# tuggerTrackerV1.net
KiCad netlist of a schematic drawn in EAGLE
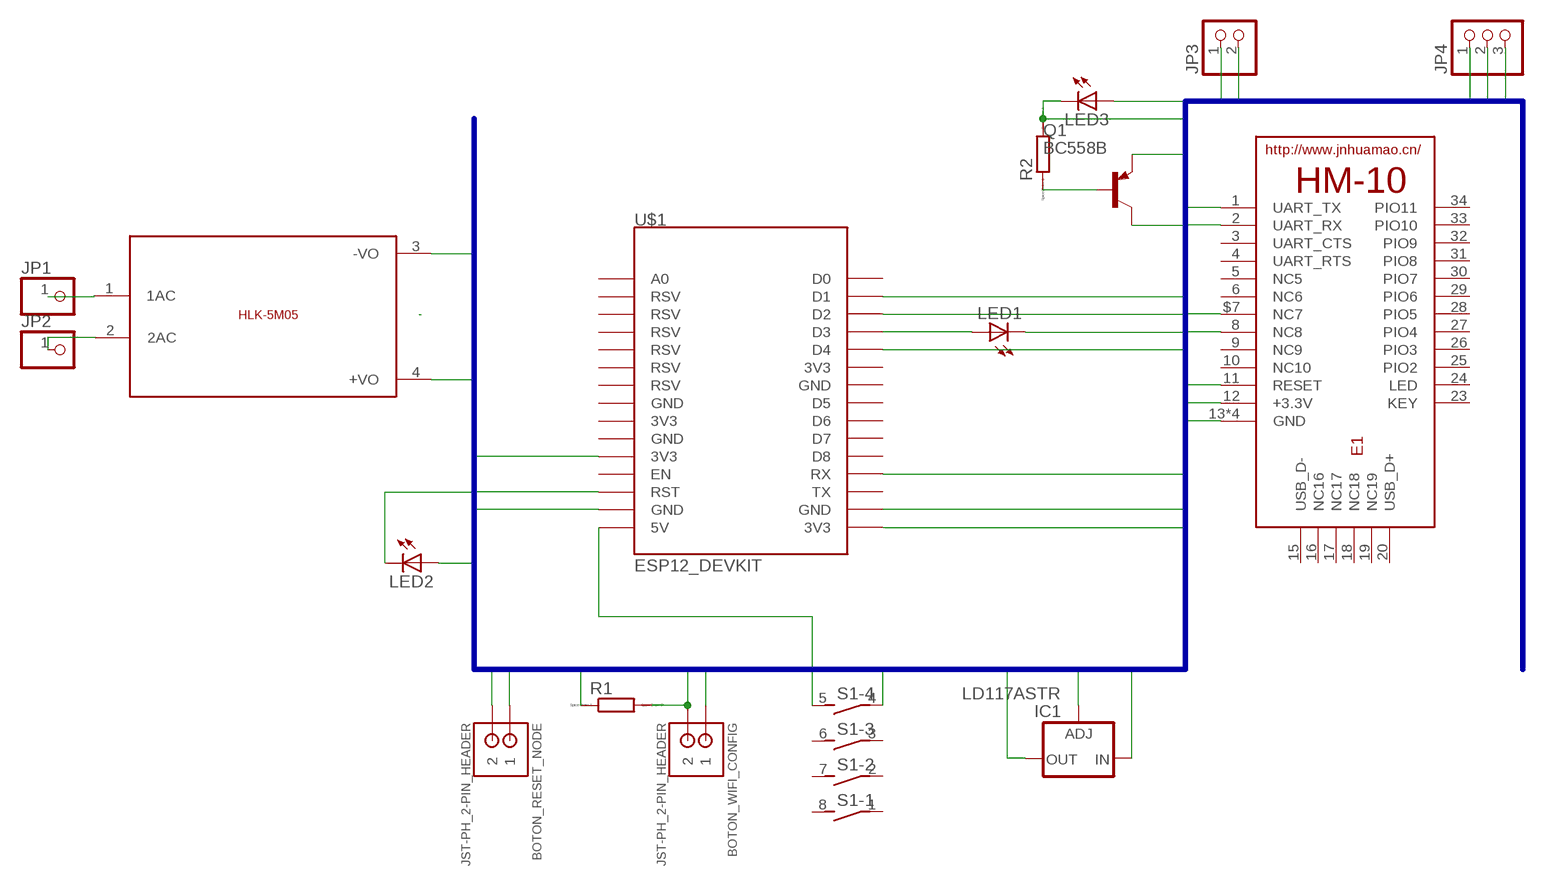
[diagram p0: schematic, sheet 1]

(export (version "E")
  (design (tool "Eeschema 10.0.6"))
  (components
    (comp (ref "BOTON_RESET_NODE")
      (value "JST-PH_2-PIN_HEADER")
      (footprint "eagle-import:JST_B2B-PH_HEADER")
      (libsource (lib "eagle-import") (part "JST-PH_2-PIN_HEADER"))
    )
    (comp (ref "BOTON_WIFI_CONFIG")
      (value "JST-PH_2-PIN_HEADER")
      (footprint "eagle-import:JST_B2B-PH_HEADER")
      (libsource (lib "eagle-import") (part "JST-PH_2-PIN_HEADER"))
    )
    (comp (ref "E1")
      (value "HM-10-BOARD")
      (footprint "eagle-import:26.9X13X2.2_BOARD")
      (libsource (lib "eagle-import") (part "HM-10-BOARD"))
    )
    (comp (ref "IC1")
      (value "LD117ASTR")
      (footprint "eagle-import:SOT223")
      (libsource (lib "eagle-import") (part "LD117A?STR"))
    )
    (comp (ref "JP1")
      (value "PINHD-1X1")
      (footprint "eagle-import:1X01")
      (libsource (lib "eagle-import") (part "PINHD-1X1"))
    )
    (comp (ref "JP2")
      (value "PINHD-1X1")
      (footprint "eagle-import:1X01")
      (libsource (lib "eagle-import") (part "PINHD-1X1"))
    )
    (comp (ref "JP3")
      (value "PINHD-1X2")
      (footprint "eagle-import:1X02")
      (libsource (lib "eagle-import") (part "PINHD-1X2"))
    )
    (comp (ref "JP4")
      (value "PINHD-1X3")
      (footprint "eagle-import:1X03")
      (libsource (lib "eagle-import") (part "PINHD-1X3"))
    )
    (comp (ref "LED1")
      (value "LEDCHIPLED_1206")
      (footprint "eagle-import:CHIPLED_1206")
      (libsource (lib "eagle-import") (part "LEDCHIPLED_1206"))
    )
    (comp (ref "LED2")
      (value "LEDCHIPLED_1206")
      (footprint "eagle-import:CHIPLED_1206")
      (libsource (lib "eagle-import") (part "LEDCHIPLED_1206"))
    )
    (comp (ref "LED3")
      (value "LEDCHIPLED_1206")
      (footprint "eagle-import:CHIPLED_1206")
      (libsource (lib "eagle-import") (part "LEDCHIPLED_1206"))
    )
    (comp (ref "Q1")
      (value "BC558B")
      (footprint "eagle-import:TO92-EBC")
      (libsource (lib "eagle-import") (part "BC558B"))
    )
    (comp (ref "R1")
      (value "R0207/10")
      (footprint "eagle-import:0207_10")
      (libsource (lib "eagle-import") (part "R0207/10"))
    )
    (comp (ref "R2")
      (value "R0207/10")
      (footprint "eagle-import:0207_10")
      (libsource (lib "eagle-import") (part "R0207/10"))
    )
    (comp (ref "S1")
      (value "DIP04S")
      (footprint "eagle-import:DIP04S")
      (libsource (lib "eagle-import") (part "DIP04S"))
    )
    (comp (ref "U$1")
      (value "ESP12_DEVKIT")
      (footprint "eagle-import:ESP12_DEVKIT")
      (libsource (lib "eagle-import") (part "ESP12_DEVKIT"))
    )
    (comp (ref "U$2")
      (value "5VDC/5W")
      (footprint "eagle-import:HLK-5M05")
      (libsource (lib "eagle-import") (part "HLK-5M05"))
    )
  )
  (nets
    (net (code "1") (name "/BTPG1") (class "Default")
      (node (ref "E1") (pin "$7") (pinfunction "NC7_$7") (pintype "bidirectional"))
      (node (ref "JP4") (pin "1") (pinfunction "1_1") (pintype "passive"))
    )
    (net (code "2") (name "/BTPG2") (class "Default")
      (node (ref "E1") (pin "8") (pinfunction "NC8_8") (pintype "bidirectional"))
      (node (ref "JP4") (pin "2") (pinfunction "2_2") (pintype "passive"))
    )
    (net (code "3") (name "/BTRST") (class "Default")
      (node (ref "E1") (pin "11") (pinfunction "RESET_11") (pintype "bidirectional"))
      (node (ref "JP4") (pin "3") (pinfunction "3_3") (pintype "passive"))
    )
    (net (code "4") (name "/BTVCC") (class "Default")
      (node (ref "E1") (pin "12") (pinfunction "+3.3V_12") (pintype "bidirectional"))
      (node (ref "Q1") (pin "C") (pinfunction "C_C") (pintype "passive"))
    )
    (net (code "5") (name "/D1") (class "Default")
      (node (ref "LED3") (pin "C") (pinfunction "C_C") (pintype "passive"))
      (node (ref "R2") (pin "2") (pinfunction "2_2") (pintype "passive"))
      (node (ref "U$1") (pin "D1") (pinfunction "D1_D1") (pintype "bidirectional"))
    )
    (net (code "6") (name "/D2") (class "Default")
      (node (ref "BOTON_WIFI_CONFIG") (pin "P2") (pinfunction "2_P2") (pintype "bidirectional"))
      (node (ref "R1") (pin "2") (pinfunction "2_2") (pintype "passive"))
      (node (ref "U$1") (pin "D2") (pinfunction "D2_D2") (pintype "bidirectional"))
    )
    (net (code "7") (name "/GND") (class "Default")
      (node (ref "BOTON_RESET_NODE") (pin "P2") (pinfunction "2_P2") (pintype "bidirectional"))
      (node (ref "E1") (pin "13") (pinfunction "GND_13") (pintype "bidirectional"))
      (node (ref "E1") (pin "14") (pinfunction "GND_14") (pintype "bidirectional"))
      (node (ref "E1") (pin "21") (pinfunction "GND_21") (pintype "bidirectional"))
      (node (ref "E1") (pin "22") (pinfunction "GND_22") (pintype "bidirectional"))
      (node (ref "IC1") (pin "1") (pinfunction "ADJ_1") (pintype "input"))
      (node (ref "JP3") (pin "1") (pinfunction "1_1") (pintype "passive"))
      (node (ref "LED1") (pin "C") (pinfunction "C_C") (pintype "passive"))
      (node (ref "LED2") (pin "C") (pinfunction "C_C") (pintype "passive"))
      (node (ref "R1") (pin "1") (pinfunction "1_1") (pintype "passive"))
      (node (ref "U$1") (pin "GND@1") (pinfunction "GND_GND@1") (pintype "bidirectional"))
      (node (ref "U$1") (pin "GND@3") (pinfunction "GND_GND@3") (pintype "bidirectional"))
      (node (ref "U$2") (pin "3") (pinfunction "-VO_3") (pintype "bidirectional"))
    )
    (net (code "8") (name "/NODRST") (class "Default")
      (node (ref "BOTON_RESET_NODE") (pin "P1") (pinfunction "1_P1") (pintype "bidirectional"))
      (node (ref "U$1") (pin "RST") (pinfunction "RST_RST") (pintype "bidirectional"))
    )
    (net (code "9") (name "/NRXBTX") (class "Default")
      (node (ref "E1") (pin "1") (pinfunction "UART_TX_1") (pintype "bidirectional"))
      (node (ref "U$1") (pin "RX") (pinfunction "RX_RX") (pintype "bidirectional"))
    )
    (net (code "10") (name "/NTXBRX") (class "Default")
      (node (ref "E1") (pin "2") (pinfunction "UART_RX_2") (pintype "bidirectional"))
      (node (ref "U$1") (pin "D4") (pinfunction "D4_D4") (pintype "bidirectional"))
    )
    (net (code "11") (name "/V3NODE") (class "Default")
      (node (ref "BOTON_WIFI_CONFIG") (pin "P1") (pinfunction "1_P1") (pintype "bidirectional"))
      (node (ref "LED2") (pin "A") (pinfunction "A_A") (pintype "passive"))
      (node (ref "LED3") (pin "A") (pinfunction "A_A") (pintype "passive"))
      (node (ref "U$1") (pin "3V3@0") (pinfunction "3V3_3V3@0") (pintype "bidirectional"))
      (node (ref "U$1") (pin "3V3@2") (pinfunction "3V3_3V3@2") (pintype "bidirectional"))
    )
    (net (code "12") (name "/V3REG") (class "Default")
      (node (ref "IC1") (pin "4") (pinfunction "OUT_4") (pintype "passive"))
      (node (ref "Q1") (pin "E") (pinfunction "E_E") (pintype "passive"))
    )
    (net (code "13") (name "/VIN") (class "Default")
      (node (ref "IC1") (pin "3") (pinfunction "IN_3") (pintype "input"))
      (node (ref "JP3") (pin "2") (pinfunction "2_2") (pintype "passive"))
      (node (ref "S1") (pin "4") (pinfunction "1_4") (pintype "passive"))
      (node (ref "U$2") (pin "4") (pinfunction "+VO_4") (pintype "bidirectional"))
    )
    (net (code "14") (name "Net-(LED1-PadA)") (class "Default")
      (node (ref "LED1") (pin "A") (pinfunction "A_A") (pintype "passive"))
      (node (ref "U$1") (pin "D3") (pinfunction "D3_D3") (pintype "bidirectional"))
    )
    (net (code "15") (name "Net-(Q1-PadB)") (class "Default")
      (node (ref "Q1") (pin "B") (pinfunction "B_B") (pintype "passive"))
      (node (ref "R2") (pin "1") (pinfunction "1_1") (pintype "passive"))
    )
    (net (code "16") (name "Net-(S1D-2)") (class "Default")
      (node (ref "S1") (pin "5") (pinfunction "2_5") (pintype "passive"))
      (node (ref "U$1") (pin "5V") (pinfunction "5V_5V") (pintype "bidirectional"))
    )
    (net (code "17") (name "Net-(U$2-1AC)") (class "Default")
      (node (ref "JP1") (pin "1") (pinfunction "1_1") (pintype "passive"))
      (node (ref "U$2") (pin "1") (pinfunction "1AC_1") (pintype "bidirectional"))
    )
    (net (code "18") (name "Net-(U$2-2AC)") (class "Default")
      (node (ref "JP2") (pin "1") (pinfunction "1_1") (pintype "passive"))
      (node (ref "U$2") (pin "2") (pinfunction "2AC_2") (pintype "bidirectional"))
    )
    (net (code "19") (name "unconnected-(E1-KEY-Pad23)") (class "Default")
      (node (ref "E1") (pin "23") (pinfunction "KEY_23") (pintype "bidirectional"))
    )
    (net (code "20") (name "unconnected-(E1-LED-Pad24)") (class "Default")
      (node (ref "E1") (pin "24") (pinfunction "LED_24") (pintype "bidirectional"))
    )
    (net (code "21") (name "unconnected-(E1-NC5-Pad5)") (class "Default")
      (node (ref "E1") (pin "5") (pinfunction "NC5_5") (pintype "bidirectional"))
    )
    (net (code "22") (name "unconnected-(E1-NC6-Pad6)") (class "Default")
      (node (ref "E1") (pin "6") (pinfunction "NC6_6") (pintype "bidirectional"))
    )
    (net (code "23") (name "unconnected-(E1-NC9-Pad9)") (class "Default")
      (node (ref "E1") (pin "9") (pinfunction "NC9_9") (pintype "bidirectional"))
    )
    (net (code "24") (name "unconnected-(E1-NC10-Pad10)") (class "Default")
      (node (ref "E1") (pin "10") (pinfunction "NC10_10") (pintype "bidirectional"))
    )
    (net (code "25") (name "unconnected-(E1-NC16-Pad16)") (class "Default")
      (node (ref "E1") (pin "16") (pinfunction "NC16_16") (pintype "bidirectional"))
    )
    (net (code "26") (name "unconnected-(E1-NC17-Pad17)") (class "Default")
      (node (ref "E1") (pin "17") (pinfunction "NC17_17") (pintype "bidirectional"))
    )
    (net (code "27") (name "unconnected-(E1-NC18-Pad18)") (class "Default")
      (node (ref "E1") (pin "18") (pinfunction "NC18_18") (pintype "bidirectional"))
    )
    (net (code "28") (name "unconnected-(E1-NC19-Pad19)") (class "Default")
      (node (ref "E1") (pin "19") (pinfunction "NC19_19") (pintype "bidirectional"))
    )
    (net (code "29") (name "unconnected-(E1-PIO2-Pad25)") (class "Default")
      (node (ref "E1") (pin "25") (pinfunction "PIO2_25") (pintype "bidirectional"))
    )
    (net (code "30") (name "unconnected-(E1-PIO3-Pad26)") (class "Default")
      (node (ref "E1") (pin "26") (pinfunction "PIO3_26") (pintype "bidirectional"))
    )
    (net (code "31") (name "unconnected-(E1-PIO4-Pad27)") (class "Default")
      (node (ref "E1") (pin "27") (pinfunction "PIO4_27") (pintype "bidirectional"))
    )
    (net (code "32") (name "unconnected-(E1-PIO5-Pad28)") (class "Default")
      (node (ref "E1") (pin "28") (pinfunction "PIO5_28") (pintype "bidirectional"))
    )
    (net (code "33") (name "unconnected-(E1-PIO6-Pad29)") (class "Default")
      (node (ref "E1") (pin "29") (pinfunction "PIO6_29") (pintype "bidirectional"))
    )
    (net (code "34") (name "unconnected-(E1-PIO7-Pad30)") (class "Default")
      (node (ref "E1") (pin "30") (pinfunction "PIO7_30") (pintype "bidirectional"))
    )
    (net (code "35") (name "unconnected-(E1-PIO8-Pad31)") (class "Default")
      (node (ref "E1") (pin "31") (pinfunction "PIO8_31") (pintype "bidirectional"))
    )
    (net (code "36") (name "unconnected-(E1-PIO9-Pad32)") (class "Default")
      (node (ref "E1") (pin "32") (pinfunction "PIO9_32") (pintype "bidirectional"))
    )
    (net (code "37") (name "unconnected-(E1-PIO10-Pad33)") (class "Default")
      (node (ref "E1") (pin "33") (pinfunction "PIO10_33") (pintype "bidirectional"))
    )
    (net (code "38") (name "unconnected-(E1-PIO11-Pad34)") (class "Default")
      (node (ref "E1") (pin "34") (pinfunction "PIO11_34") (pintype "bidirectional"))
    )
    (net (code "39") (name "unconnected-(E1-UART_CTS-Pad3)") (class "Default")
      (node (ref "E1") (pin "3") (pinfunction "UART_CTS_3") (pintype "bidirectional"))
    )
    (net (code "40") (name "unconnected-(E1-UART_RTS-Pad4)") (class "Default")
      (node (ref "E1") (pin "4") (pinfunction "UART_RTS_4") (pintype "bidirectional"))
    )
    (net (code "41") (name "unconnected-(E1-USB_D+-Pad20)") (class "Default")
      (node (ref "E1") (pin "20") (pinfunction "USB_D+_20") (pintype "bidirectional"))
    )
    (net (code "42") (name "unconnected-(E1-USB_D--Pad15)") (class "Default")
      (node (ref "E1") (pin "15") (pinfunction "USB_D-_15") (pintype "bidirectional"))
    )
    (net (code "43") (name "unconnected-(S1-Pad1)") (class "Default")
      (node (ref "S1") (pin "1") (pinfunction "1_1") (pintype "passive"))
    )
    (net (code "44") (name "unconnected-(S1A-2-Pad8)") (class "Default")
      (node (ref "S1") (pin "8") (pinfunction "2_8") (pintype "passive"))
    )
    (net (code "45") (name "unconnected-(S1B-1-Pad2)") (class "Default")
      (node (ref "S1") (pin "2") (pinfunction "1_2") (pintype "passive"))
    )
    (net (code "46") (name "unconnected-(S1B-2-Pad7)") (class "Default")
      (node (ref "S1") (pin "7") (pinfunction "2_7") (pintype "passive"))
    )
    (net (code "47") (name "unconnected-(S1C-1-Pad3)") (class "Default")
      (node (ref "S1") (pin "3") (pinfunction "1_3") (pintype "passive"))
    )
    (net (code "48") (name "unconnected-(S1C-2-Pad6)") (class "Default")
      (node (ref "S1") (pin "6") (pinfunction "2_6") (pintype "passive"))
    )
    (net (code "49") (name "unconnected-(U$1-3V3-Pad3V3@1)") (class "Default")
      (node (ref "U$1") (pin "3V3@1") (pinfunction "3V3_3V3@1") (pintype "bidirectional"))
    )
    (net (code "50") (name "unconnected-(U$1-3V3-Pad3V3@3)") (class "Default")
      (node (ref "U$1") (pin "3V3@3") (pinfunction "3V3_3V3@3") (pintype "bidirectional"))
    )
    (net (code "51") (name "unconnected-(U$1-GND-PadGND@0)") (class "Default")
      (node (ref "U$1") (pin "GND@0") (pinfunction "GND_GND@0") (pintype "bidirectional"))
    )
    (net (code "52") (name "unconnected-(U$1-GND-PadGND@2)") (class "Default")
      (node (ref "U$1") (pin "GND@2") (pinfunction "GND_GND@2") (pintype "bidirectional"))
    )
    (net (code "53") (name "unconnected-(U$1-GND-PadGND@4)") (class "Default")
      (node (ref "U$1") (pin "GND@4") (pinfunction "GND_GND@4") (pintype "bidirectional"))
    )
    (net (code "54") (name "unconnected-(U$1-PadA0)") (class "Default")
      (node (ref "U$1") (pin "A0") (pinfunction "A0_A0") (pintype "bidirectional"))
    )
    (net (code "55") (name "unconnected-(U$1-PadD0)") (class "Default")
      (node (ref "U$1") (pin "D0") (pinfunction "D0_D0") (pintype "bidirectional"))
    )
    (net (code "56") (name "unconnected-(U$1-PadD5)") (class "Default")
      (node (ref "U$1") (pin "D5") (pinfunction "D5_D5") (pintype "bidirectional"))
    )
    (net (code "57") (name "unconnected-(U$1-PadD6)") (class "Default")
      (node (ref "U$1") (pin "D6") (pinfunction "D6_D6") (pintype "bidirectional"))
    )
    (net (code "58") (name "unconnected-(U$1-PadD7)") (class "Default")
      (node (ref "U$1") (pin "D7") (pinfunction "D7_D7") (pintype "bidirectional"))
    )
    (net (code "59") (name "unconnected-(U$1-PadD8)") (class "Default")
      (node (ref "U$1") (pin "D8") (pinfunction "D8_D8") (pintype "bidirectional"))
    )
    (net (code "60") (name "unconnected-(U$1-PadEN)") (class "Default")
      (node (ref "U$1") (pin "EN") (pinfunction "EN_EN") (pintype "bidirectional"))
    )
    (net (code "61") (name "unconnected-(U$1-PadTX)") (class "Default")
      (node (ref "U$1") (pin "TX") (pinfunction "TX_TX") (pintype "bidirectional"))
    )
    (net (code "62") (name "unconnected-(U$1-RSV-PadRSV@0)") (class "Default")
      (node (ref "U$1") (pin "RSV@0") (pinfunction "RSV_RSV@0") (pintype "bidirectional"))
    )
    (net (code "63") (name "unconnected-(U$1-RSV-PadRSV@1)") (class "Default")
      (node (ref "U$1") (pin "RSV@1") (pinfunction "RSV_RSV@1") (pintype "bidirectional"))
    )
    (net (code "64") (name "unconnected-(U$1-RSV-PadRSV@2)") (class "Default")
      (node (ref "U$1") (pin "RSV@2") (pinfunction "RSV_RSV@2") (pintype "bidirectional"))
    )
    (net (code "65") (name "unconnected-(U$1-RSV-PadRSV@3)") (class "Default")
      (node (ref "U$1") (pin "RSV@3") (pinfunction "RSV_RSV@3") (pintype "bidirectional"))
    )
    (net (code "66") (name "unconnected-(U$1-RSV-PadRSV@4)") (class "Default")
      (node (ref "U$1") (pin "RSV@4") (pinfunction "RSV_RSV@4") (pintype "bidirectional"))
    )
    (net (code "67") (name "unconnected-(U$1-RSV-PadRSV@5)") (class "Default")
      (node (ref "U$1") (pin "RSV@5") (pinfunction "RSV_RSV@5") (pintype "bidirectional"))
    )
  )
)
